# Xbee.net
KiCad netlist of a schematic drawn in Altium Designer
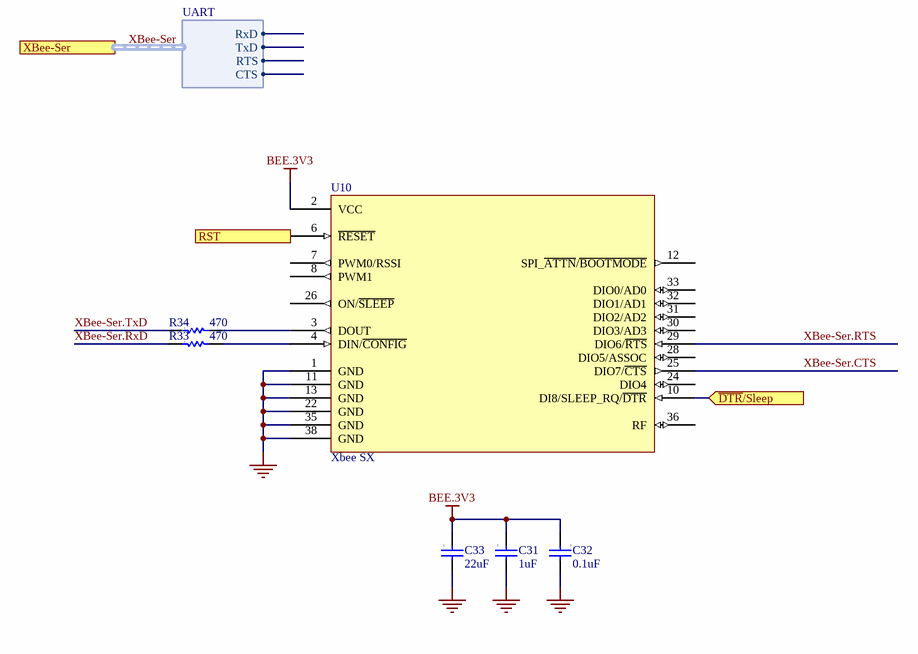
[diagram p0: Xbee.SchDoc]

(export (version "E")
  (design (tool "Eeschema 10.0.6"))
  (components
    (comp (ref "C31")
      (value "1uF")
      (footprint "0603")
      (description "CAP CER 1UF 25V X7R 0603")
      (fields
        (field (name "MANUFACTURER") "Samsung")
        (field (name "MANUFACTURER PART NUMBER") "CL10B105KA8NNNC")
        (field (name "PUBLISHER") "Altium Limited")
      )
      (libsource (lib "") (part "Cap_1"))
    )
    (comp (ref "C32")
      (value "0.1uF")
      (footprint "0402")
      (description "CAP CER .10UF 50V X7R 10% 0402")
      (fields
        (field (name "MANUFACTURER") "TDK Corporation")
        (field (name "MANUFACTURER PART NUMBER") "C1005X7R1H104K")
        (field (name "PUBLISHER") "Altium Limited")
      )
      (libsource (lib "General") (part "Cap"))
    )
    (comp (ref "C33")
      (value "22uF")
      (footprint "1206")
      (description "CAP CER 22UF 10V X5R 1206")
      (fields
        (field (name "MANUFACTURER") "Samsung")
        (field (name "MANUFACTURER PART NUMBER") "CL31A226KPHNNNE")
      )
      (libsource (lib "") (part "Cap_1"))
    )
    (comp (ref "R33")
      (value "470")
      (footprint "R0402")
      (description "RES 470 OHM 1/16W 1% 0402 SMD")
      (fields
        (field (name "MANUFACTURER") "Vishay Dale")
        (field (name "MANUFACTURER PART NUMBER") "CRCW0402470RFKED")
      )
      (libsource (lib "General") (part "Res"))
    )
    (comp (ref "R34")
      (value "470")
      (footprint "R0402")
      (description "RES 470 OHM 1/16W 1% 0402 SMD")
      (fields
        (field (name "MANUFACTURER") "Vishay Dale")
        (field (name "MANUFACTURER PART NUMBER") "CRCW0402470RFKED")
      )
      (libsource (lib "General") (part "Res"))
    )
    (comp (ref "U10")
      (value "Xbee SX")
      (footprint "XBP9X-DMUS-001")
      (description "XBEE PRO MOD TXRX ISM 915MHZ UFL")
      (fields
        (field (name "MANUFACTURER") "Digi International")
        (field (name "MANUFACTURER PART NUMBER") "XBP9X-DMUS-001")
      )
      (libsource (lib "General") (part "Xbee SX"))
    )
  )
  (nets
    (net (code "2") (name "/RST") (class "Default")
      (node (ref "U10") (pin "6") (pinfunction "~{RESET}_6") (pintype "input"))
    )
    (net (code "3") (name "/XBee-Ser.CTS") (class "Default")
      (node (ref "U10") (pin "25") (pinfunction "DIO7/~{CTS}_25") (pintype "output"))
    )
    (net (code "4") (name "/XBee-Ser.RTS") (class "Default")
      (node (ref "U10") (pin "29") (pinfunction "DIO6/~{RTS}_29") (pintype "input"))
    )
    (net (code "5") (name "/XBee-Ser.RxD") (class "Default")
      (node (ref "R33") (pin "1") (pinfunction "1_1") (pintype "passive"))
    )
    (net (code "6") (name "/XBee-Ser.TxD") (class "Default")
      (node (ref "R34") (pin "1") (pinfunction "1_1") (pintype "passive"))
    )
    (net (code "8") (name "/~{DTR}{slash}Sleep") (class "Default")
      (node (ref "U10") (pin "10") (pinfunction "DI8/SLEEP_RQ/~{DTR}_10") (pintype "input"))
    )
    (net (code "9") (name "BEE.3V3") (class "Default")
      (node (ref "C31") (pin "1") (pinfunction "1_1") (pintype "passive"))
      (node (ref "C32") (pin "1") (pinfunction "1_1") (pintype "passive"))
      (node (ref "C33") (pin "1") (pinfunction "1_1") (pintype "passive"))
      (node (ref "U10") (pin "2") (pinfunction "VCC_2") (pintype "power_in"))
    )
    (net (code "10") (name "GND") (class "Default")
      (node (ref "C31") (pin "2") (pinfunction "2_2") (pintype "passive"))
      (node (ref "C32") (pin "2") (pinfunction "2_2") (pintype "passive"))
      (node (ref "C33") (pin "2") (pinfunction "2_2") (pintype "passive"))
      (node (ref "U10") (pin "1") (pinfunction "GND_1") (pintype "power_in"))
      (node (ref "U10") (pin "11") (pinfunction "GND_11") (pintype "power_in"))
      (node (ref "U10") (pin "13") (pinfunction "GND_13") (pintype "power_in"))
      (node (ref "U10") (pin "22") (pinfunction "GND_22") (pintype "power_in"))
      (node (ref "U10") (pin "35") (pinfunction "GND_35") (pintype "power_in"))
      (node (ref "U10") (pin "38") (pinfunction "GND_38") (pintype "power_in"))
    )
    (net (code "11") (name "Net-(U10-DIN{slash}~{CONFIG})") (class "Default")
      (node (ref "R33") (pin "2") (pinfunction "2_2") (pintype "passive"))
      (node (ref "U10") (pin "4") (pinfunction "DIN/~{CONFIG}_4") (pintype "input"))
    )
    (net (code "12") (name "Net-(U10-DOUT)") (class "Default")
      (node (ref "R34") (pin "2") (pinfunction "2_2") (pintype "passive"))
      (node (ref "U10") (pin "3") (pinfunction "DOUT_3") (pintype "output"))
    )
    (net (code "13") (name "unconnected-(U10-DIO0{slash}AD0-Pad33)") (class "Default")
      (node (ref "U10") (pin "33") (pinfunction "DIO0/AD0_33") (pintype "bidirectional"))
    )
    (net (code "14") (name "unconnected-(U10-DIO1{slash}AD1-Pad32)") (class "Default")
      (node (ref "U10") (pin "32") (pinfunction "DIO1/AD1_32") (pintype "bidirectional"))
    )
    (net (code "15") (name "unconnected-(U10-DIO2{slash}AD2-Pad31)") (class "Default")
      (node (ref "U10") (pin "31") (pinfunction "DIO2/AD2_31") (pintype "bidirectional"))
    )
    (net (code "16") (name "unconnected-(U10-DIO3{slash}AD3-Pad30)") (class "Default")
      (node (ref "U10") (pin "30") (pinfunction "DIO3/AD3_30") (pintype "bidirectional"))
    )
    (net (code "17") (name "unconnected-(U10-DIO4-Pad24)") (class "Default")
      (node (ref "U10") (pin "24") (pinfunction "DIO4_24") (pintype "bidirectional"))
    )
    (net (code "18") (name "unconnected-(U10-DIO5{slash}ASSOC-Pad28)") (class "Default")
      (node (ref "U10") (pin "28") (pinfunction "DIO5/ASSOC_28") (pintype "bidirectional"))
    )
    (net (code "19") (name "unconnected-(U10-ON{slash}~{SLEEP}-Pad26)") (class "Default")
      (node (ref "U10") (pin "26") (pinfunction "ON/~{SLEEP}_26") (pintype "output"))
    )
    (net (code "20") (name "unconnected-(U10-PWM0{slash}RSSI-Pad7)") (class "Default")
      (node (ref "U10") (pin "7") (pinfunction "PWM0/RSSI_7") (pintype "output"))
    )
    (net (code "21") (name "unconnected-(U10-PWM1-Pad8)") (class "Default")
      (node (ref "U10") (pin "8") (pinfunction "PWM1_8") (pintype "output"))
    )
    (net (code "22") (name "unconnected-(U10-RF-Pad36)") (class "Default")
      (node (ref "U10") (pin "36") (pinfunction "RF_36") (pintype "bidirectional"))
    )
    (net (code "23") (name "unconnected-(U10-SPI_~{ATTN}{slash}~{BOOTMODE}-Pad12)") (class "Default")
      (node (ref "U10") (pin "12") (pinfunction "SPI_~{ATTN}/~{BOOTMODE}_12") (pintype "output"))
    )
  )
)
